# 03_-_SCHEMATIC.net
KiCad netlist of a schematic drawn in Altium Designer
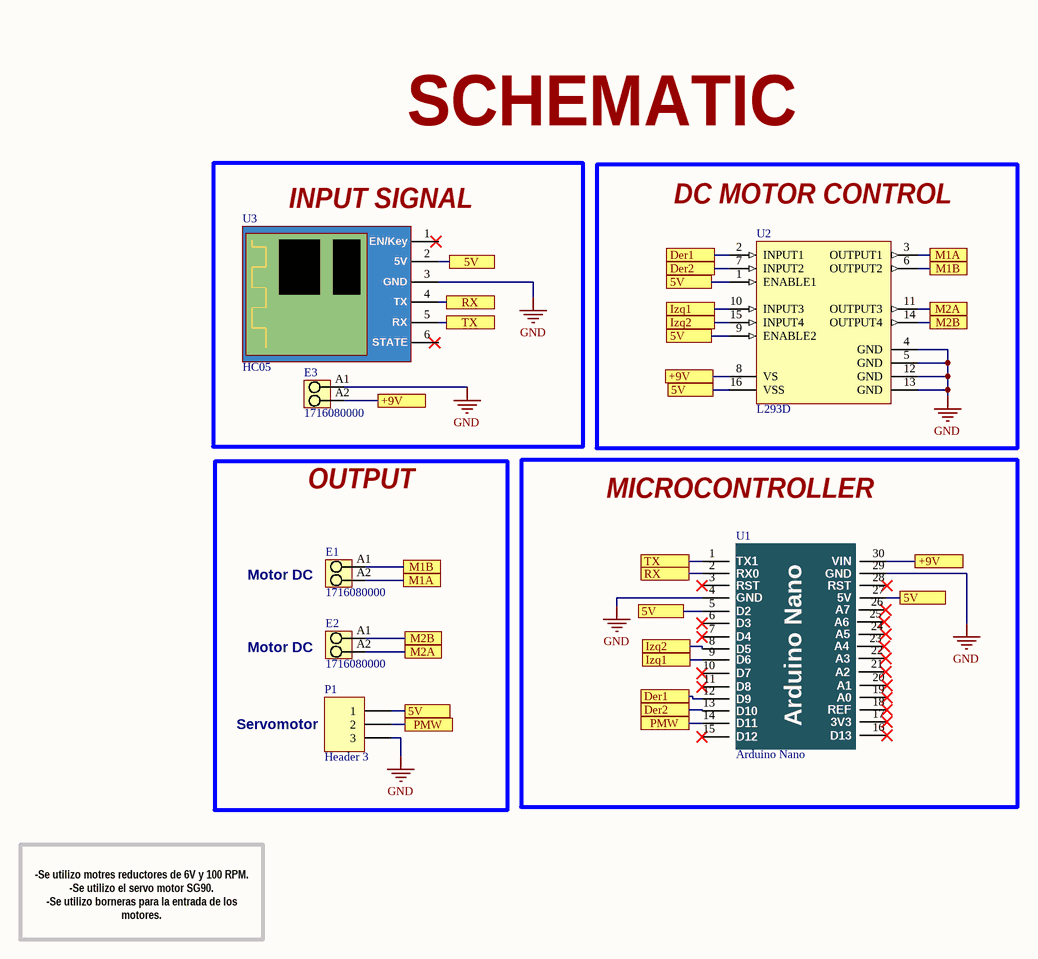
[diagram p0: [03] - SCHEMATIC.SchDoc]

(export (version "E")
  (design (tool "Eeschema 10.0.6"))
  (components
    (comp (ref "E1")
      (value "1716080000")
      (footprint "LM_5_08_90_02")
      (description "OMNIMATE Signal - series LM")
      (fields (field (name "MANUFACTURER") "Weidmueller"))
      (libsource (lib "Components_Bornera") (part "CMP-1559-01766-1"))
    )
    (comp (ref "E2")
      (value "1716080000")
      (footprint "LM_5_08_90_02")
      (description "OMNIMATE Signal - series LM")
      (fields (field (name "MANUFACTURER") "Weidmueller"))
      (libsource (lib "Components_Bornera") (part "CMP-1559-01766-1"))
    )
    (comp (ref "E3")
      (value "1716080000")
      (footprint "LM_5_08_90_02")
      (description "OMNIMATE Signal - series LM")
      (fields (field (name "MANUFACTURER") "Weidmueller"))
      (libsource (lib "Components_Bornera") (part "CMP-1559-01766-1"))
    )
    (comp (ref "P1")
      (value "Header 3")
      (footprint "HDR1X3")
      (description "Header, 3-Pin")
      (fields (field (name "PUBLISHER") "Altium Limited"))
      (libsource (lib "Miscellaneous Connectors") (part "Header 3"))
    )
    (comp (ref "U1")
      (value "Arduino Nano")
      (footprint "Arduino Nano")
      (fields (field (name "MANUFACTURER") "Arduino") (field (name "MANUFACTURER PART NUMBER") "A000005"))
      (libsource (lib "Arduino") (part "Arduino Nano"))
    )
    (comp (ref "U2")
      (value "L293D")
      (footprint "STM-L293D-16")
      (description "Push-Pull Four Channel Driver with Diode, 4.5 to 36 V, -40 to 150 degC, 16-Pin PDIP, RoHS, Tube")
      (fields (field (name "MANUFACTURER") "STMicroelectronics"))
      (libsource (lib "Components - 23.04.21 - 17.26") (part "CMP-2000-06524-1"))
    )
    (comp (ref "U3")
      (value "HC05")
      (footprint "HC05")
      (fields
        (field (name "MANUFACTURER") "Amphenol")
        (field (name "MANUFACTURER PART NUMBER") "HC05B2800000G")
        (field (name "VOLTAGE") "300V")
      )
      (libsource (lib "Arduino") (part "HC05B2800000G"))
    )
  )
  (nets
    (net (code "1") (name "/+9V") (class "Default")
      (node (ref "E3") (pin "A2") (pinfunction "GND_A2") (pintype "passive"))
      (node (ref "U1") (pin "30") (pinfunction "VIN_30") (pintype "passive"))
      (node (ref "U2") (pin "8") (pinfunction "VS_8") (pintype "power_in"))
    )
    (net (code "2") (name "/5V") (class "Default")
      (node (ref "P1") (pin "1") (pinfunction "1_1") (pintype "passive"))
      (node (ref "U1") (pin "27") (pinfunction "5V_27") (pintype "passive"))
      (node (ref "U1") (pin "5") (pinfunction "D2_5") (pintype "passive"))
      (node (ref "U2") (pin "1") (pinfunction "ENABLE1_1") (pintype "input"))
      (node (ref "U2") (pin "16") (pinfunction "VSS_16") (pintype "power_in"))
      (node (ref "U2") (pin "9") (pinfunction "ENABLE2_9") (pintype "input"))
      (node (ref "U3") (pin "2") (pinfunction "5V_2") (pintype "passive"))
    )
    (net (code "3") (name "/Der1") (class "Default")
      (node (ref "U1") (pin "12") (pinfunction "D9_12") (pintype "passive"))
      (node (ref "U2") (pin "2") (pinfunction "INPUT1_2") (pintype "input"))
    )
    (net (code "4") (name "/Der2") (class "Default")
      (node (ref "U1") (pin "13") (pinfunction "D10_13") (pintype "passive"))
      (node (ref "U2") (pin "7") (pinfunction "INPUT2_7") (pintype "input"))
    )
    (net (code "5") (name "/Izq1") (class "Default")
      (node (ref "U1") (pin "9") (pinfunction "D6_9") (pintype "passive"))
      (node (ref "U2") (pin "10") (pinfunction "INPUT3_10") (pintype "input"))
    )
    (net (code "6") (name "/Izq2") (class "Default")
      (node (ref "U1") (pin "8") (pinfunction "D5_8") (pintype "passive"))
      (node (ref "U2") (pin "15") (pinfunction "INPUT4_15") (pintype "input"))
    )
    (net (code "7") (name "/M1A") (class "Default")
      (node (ref "E1") (pin "A2") (pinfunction "GND_A2") (pintype "passive"))
      (node (ref "U2") (pin "3") (pinfunction "OUTPUT1_3") (pintype "output"))
    )
    (net (code "8") (name "/M1B") (class "Default")
      (node (ref "E1") (pin "A1") (pinfunction "9V_A1") (pintype "passive"))
      (node (ref "U2") (pin "6") (pinfunction "OUTPUT2_6") (pintype "output"))
    )
    (net (code "9") (name "/M2A") (class "Default")
      (node (ref "E2") (pin "A2") (pinfunction "GND_A2") (pintype "passive"))
      (node (ref "U2") (pin "11") (pinfunction "OUTPUT3_11") (pintype "output"))
    )
    (net (code "10") (name "/M2B") (class "Default")
      (node (ref "E2") (pin "A1") (pinfunction "9V_A1") (pintype "passive"))
      (node (ref "U2") (pin "14") (pinfunction "OUTPUT4_14") (pintype "output"))
    )
    (net (code "11") (name "/PMW") (class "Default")
      (node (ref "P1") (pin "2") (pinfunction "2_2") (pintype "passive"))
      (node (ref "U1") (pin "14") (pinfunction "D11_14") (pintype "passive"))
    )
    (net (code "12") (name "/RX") (class "Default")
      (node (ref "U1") (pin "2") (pinfunction "RX0_2") (pintype "passive"))
      (node (ref "U3") (pin "4") (pinfunction "TX_4") (pintype "passive"))
    )
    (net (code "13") (name "/TX") (class "Default")
      (node (ref "U1") (pin "1") (pinfunction "TX1_1") (pintype "passive"))
      (node (ref "U3") (pin "5") (pinfunction "RX_5") (pintype "passive"))
    )
    (net (code "14") (name "GND") (class "Default")
      (node (ref "E3") (pin "A1") (pinfunction "9V_A1") (pintype "passive"))
      (node (ref "P1") (pin "3") (pinfunction "3_3") (pintype "passive"))
      (node (ref "U1") (pin "29") (pinfunction "GND_29") (pintype "passive"))
      (node (ref "U1") (pin "4") (pinfunction "GND_4") (pintype "passive"))
      (node (ref "U2") (pin "12") (pinfunction "GND_12") (pintype "power_in"))
      (node (ref "U2") (pin "13") (pinfunction "GND_13") (pintype "power_in"))
      (node (ref "U2") (pin "4") (pinfunction "GND_4") (pintype "power_in"))
      (node (ref "U2") (pin "5") (pinfunction "GND_5") (pintype "power_in"))
      (node (ref "U3") (pin "3") (pinfunction "GND_3") (pintype "passive"))
    )
    (net (code "15") (name "unconnected-(U1-3V3-Pad17)") (class "Default")
      (node (ref "U1") (pin "17") (pinfunction "3V3_17") (pintype "passive+no_connect"))
    )
    (net (code "16") (name "unconnected-(U1-A0-Pad19)") (class "Default")
      (node (ref "U1") (pin "19") (pinfunction "A0_19") (pintype "passive+no_connect"))
    )
    (net (code "17") (name "unconnected-(U1-A1-Pad20)") (class "Default")
      (node (ref "U1") (pin "20") (pinfunction "A1_20") (pintype "passive+no_connect"))
    )
    (net (code "18") (name "unconnected-(U1-A2-Pad21)") (class "Default")
      (node (ref "U1") (pin "21") (pinfunction "A2_21") (pintype "passive+no_connect"))
    )
    (net (code "19") (name "unconnected-(U1-A3-Pad22)") (class "Default")
      (node (ref "U1") (pin "22") (pinfunction "A3_22") (pintype "passive+no_connect"))
    )
    (net (code "20") (name "unconnected-(U1-A4-Pad23)") (class "Default")
      (node (ref "U1") (pin "23") (pinfunction "A4_23") (pintype "passive+no_connect"))
    )
    (net (code "21") (name "unconnected-(U1-A5-Pad24)") (class "Default")
      (node (ref "U1") (pin "24") (pinfunction "A5_24") (pintype "passive+no_connect"))
    )
    (net (code "22") (name "unconnected-(U1-A6-Pad25)") (class "Default")
      (node (ref "U1") (pin "25") (pinfunction "A6_25") (pintype "passive+no_connect"))
    )
    (net (code "23") (name "unconnected-(U1-A7-Pad26)") (class "Default")
      (node (ref "U1") (pin "26") (pinfunction "A7_26") (pintype "passive+no_connect"))
    )
    (net (code "24") (name "unconnected-(U1-D3-Pad6)") (class "Default")
      (node (ref "U1") (pin "6") (pinfunction "D3_6") (pintype "passive+no_connect"))
    )
    (net (code "25") (name "unconnected-(U1-D4-Pad7)") (class "Default")
      (node (ref "U1") (pin "7") (pinfunction "D4_7") (pintype "passive+no_connect"))
    )
    (net (code "26") (name "unconnected-(U1-D7-Pad10)") (class "Default")
      (node (ref "U1") (pin "10") (pinfunction "D7_10") (pintype "passive+no_connect"))
    )
    (net (code "27") (name "unconnected-(U1-D8-Pad11)") (class "Default")
      (node (ref "U1") (pin "11") (pinfunction "D8_11") (pintype "passive+no_connect"))
    )
    (net (code "28") (name "unconnected-(U1-D12-Pad15)") (class "Default")
      (node (ref "U1") (pin "15") (pinfunction "D12_15") (pintype "passive+no_connect"))
    )
    (net (code "29") (name "unconnected-(U1-D13-Pad16)") (class "Default")
      (node (ref "U1") (pin "16") (pinfunction "D13_16") (pintype "passive+no_connect"))
    )
    (net (code "30") (name "unconnected-(U1-REF-Pad18)") (class "Default")
      (node (ref "U1") (pin "18") (pinfunction "REF_18") (pintype "passive+no_connect"))
    )
    (net (code "31") (name "unconnected-(U1-RST-Pad3)") (class "Default")
      (node (ref "U1") (pin "3") (pinfunction "RST_3") (pintype "passive+no_connect"))
    )
    (net (code "32") (name "unconnected-(U1-RST-Pad28)") (class "Default")
      (node (ref "U1") (pin "28") (pinfunction "RST_28") (pintype "passive+no_connect"))
    )
    (net (code "33") (name "unconnected-(U3-EN{slash}Key-Pad1)") (class "Default")
      (node (ref "U3") (pin "1") (pinfunction "EN/Key_1") (pintype "passive"))
    )
    (net (code "34") (name "unconnected-(U3-STATE-Pad6)") (class "Default")
      (node (ref "U3") (pin "6") (pinfunction "STATE_6") (pintype "passive"))
    )
  )
)
